# stirrer.net
KiCad netlist of a schematic drawn in EAGLE
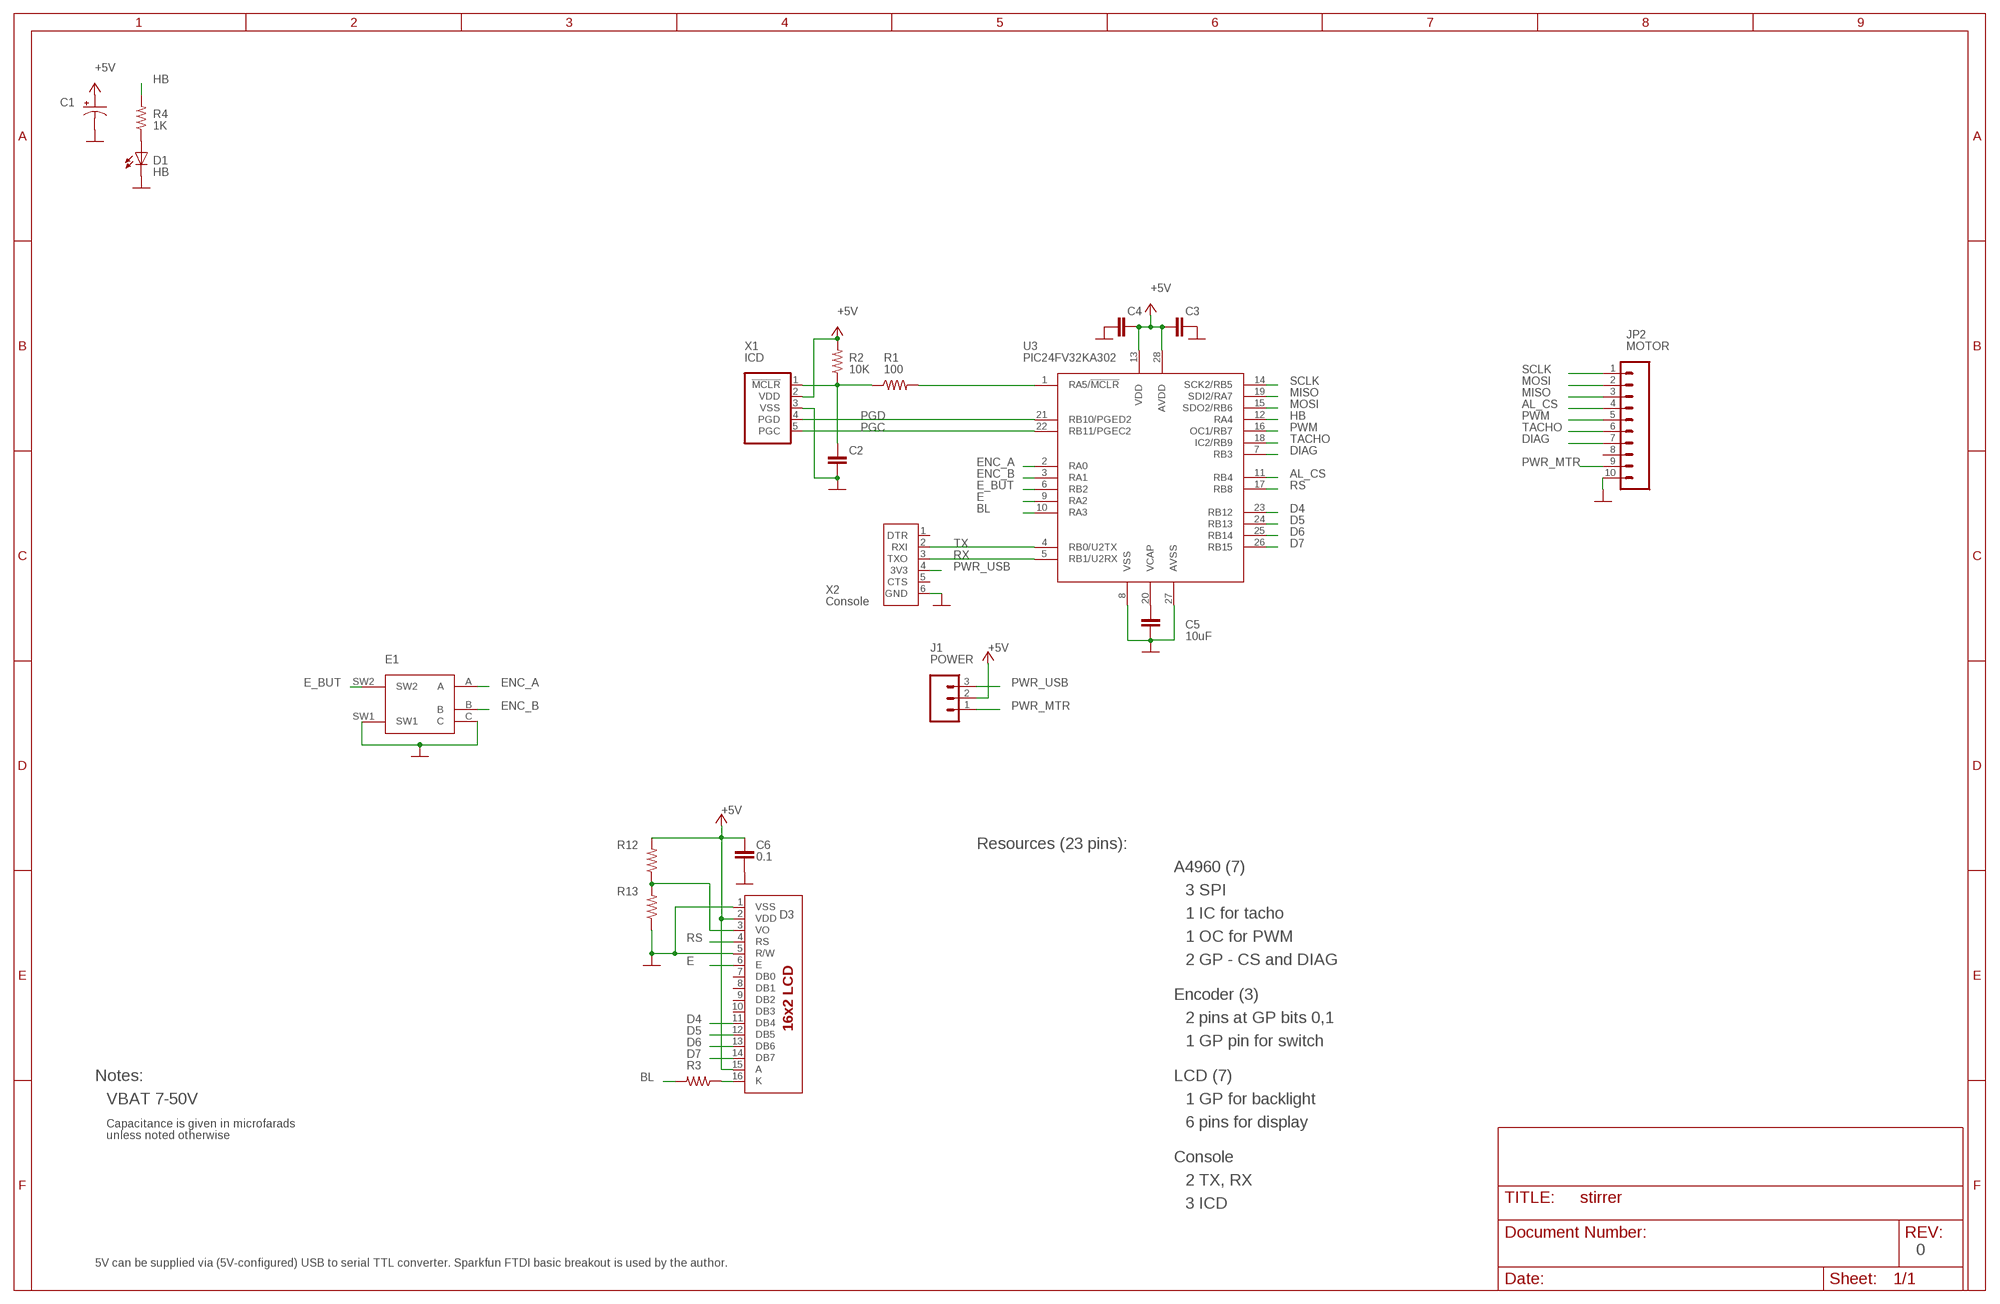
[diagram p0: schematic, sheet 1]

(export (version "E")
  (design (tool "Eeschema 10.0.6"))
  (components
    (comp (ref "C1")
      (value "CAP_POL-RAD4")
      (footprint "eagle-import:CAP_RAD_4MM")
      (libsource (lib "eagle-import") (part "CAP_POL-RAD4"))
    )
    (comp (ref "C2")
      (value "0.1uF")
      (footprint "eagle-import:CAP-PTH-SMALL")
      (libsource (lib "eagle-import") (part "CAPPTH"))
    )
    (comp (ref "C3")
      (value "0.1uF")
      (footprint "eagle-import:CAP-PTH-SMALL")
      (libsource (lib "eagle-import") (part "CAPPTH"))
    )
    (comp (ref "C4")
      (value "0.1uF")
      (footprint "eagle-import:CAP-PTH-SMALL")
      (libsource (lib "eagle-import") (part "CAPPTH"))
    )
    (comp (ref "C5")
      (value "10uF")
      (footprint "eagle-import:CAP-PTH-SMALL")
      (libsource (lib "eagle-import") (part "CAPPTH"))
    )
    (comp (ref "C6")
      (value "0.1")
      (footprint "eagle-import:CAP-PTH-SMALL")
      (libsource (lib "eagle-import") (part "CAPPTH"))
    )
    (comp (ref "D1")
      (value "HB")
      (footprint "eagle-import:LED5MM")
      (libsource (lib "eagle-import") (part "LED5MM"))
    )
    (comp (ref "D3")
      (value "LCD-16X2-STD")
      (footprint "eagle-import:LCD-16X2")
      (libsource (lib "eagle-import") (part "LCD-16X2-STD"))
    )
    (comp (ref "E1")
      (value "ROTARY_ENCODER_SWITCH-PEC12_HOR")
      (footprint "eagle-import:ENC_12X14MM_SW_HOR")
      (libsource (lib "eagle-import") (part "ROTARY_ENCODER_SWITCH-PEC12_HOR"))
    )
    (comp (ref "J1")
      (value "POWER")
      (footprint "eagle-import:1X03")
      (libsource (lib "eagle-import") (part "M03PTH"))
    )
    (comp (ref "JP2")
      (value "MOTOR")
      (footprint "eagle-import:1X10")
      (libsource (lib "eagle-import") (part "M100.1"))
    )
    (comp (ref "R1")
      (value "100")
      (footprint "eagle-import:AXIAL-0.4")
      (libsource (lib "eagle-import") (part "RESISTOR-PTH04"))
    )
    (comp (ref "R2")
      (value "10K")
      (footprint "eagle-import:AXIAL-0.4")
      (libsource (lib "eagle-import") (part "RESISTOR-PTH04"))
    )
    (comp (ref "R3")
      (value "RESISTOR-PTH04")
      (footprint "eagle-import:AXIAL-0.4")
      (libsource (lib "eagle-import") (part "RESISTOR-PTH04"))
    )
    (comp (ref "R4")
      (value "1K")
      (footprint "eagle-import:AXIAL-0.4")
      (libsource (lib "eagle-import") (part "RESISTOR-PTH04"))
    )
    (comp (ref "R12")
      (value "RESISTOR-PTH04")
      (footprint "eagle-import:AXIAL-0.4")
      (libsource (lib "eagle-import") (part "RESISTOR-PTH04"))
    )
    (comp (ref "R13")
      (value "RESISTOR-PTH04")
      (footprint "eagle-import:AXIAL-0.4")
      (libsource (lib "eagle-import") (part "RESISTOR-PTH04"))
    )
    (comp (ref "U3")
      (value "PIC24FV32KA302")
      (footprint "eagle-import:DIL28-3")
      (libsource (lib "eagle-import") (part "PIC24FV32KA302_STIR-DIP"))
    )
    (comp (ref "X1")
      (value "ICD")
      (footprint "eagle-import:1X05")
      (libsource (lib "eagle-import") (part "PIC_ICD-STRAIGHT"))
    )
    (comp (ref "X2")
      (value "Console")
      (footprint "eagle-import:1X06")
      (libsource (lib "eagle-import") (part "SERIAL-SF"))
    )
  )
  (nets
    (net (code "1") (name "+5V") (class "Default")
      (node (ref "C1") (pin "P") (pinfunction "+_P") (pintype "passive"))
      (node (ref "C3") (pin "1") (pinfunction "1_1") (pintype "passive"))
      (node (ref "C4") (pin "2") (pinfunction "2_2") (pintype "passive"))
      (node (ref "C6") (pin "2") (pinfunction "2_2") (pintype "passive"))
      (node (ref "D3") (pin "15") (pinfunction "A_15") (pintype "power_in"))
      (node (ref "D3") (pin "2") (pinfunction "VDD_2") (pintype "power_in"))
      (node (ref "J1") (pin "2") (pinfunction "2_2") (pintype "passive"))
      (node (ref "R12") (pin "P$2") (pinfunction "2_P$2") (pintype "passive"))
      (node (ref "R2") (pin "P$2") (pinfunction "2_P$2") (pintype "passive"))
      (node (ref "U3") (pin "13") (pinfunction "VDD_13") (pintype "bidirectional"))
      (node (ref "U3") (pin "28") (pinfunction "AVDD_28") (pintype "bidirectional"))
      (node (ref "X1") (pin "2") (pinfunction "VDD_2") (pintype "passive"))
    )
    (net (code "2") (name "/AL_CS") (class "Default")
      (node (ref "JP2") (pin "4") (pinfunction "4_4") (pintype "passive"))
      (node (ref "U3") (pin "11") (pinfunction "RB4_11") (pintype "bidirectional"))
    )
    (net (code "3") (name "/BL") (class "Default")
      (node (ref "R3") (pin "P$2") (pinfunction "2_P$2") (pintype "passive"))
      (node (ref "U3") (pin "10") (pinfunction "RA3_10") (pintype "bidirectional"))
    )
    (net (code "4") (name "/D4") (class "Default")
      (node (ref "D3") (pin "11") (pinfunction "DB4_11") (pintype "bidirectional"))
      (node (ref "U3") (pin "23") (pinfunction "RB12_23") (pintype "bidirectional"))
    )
    (net (code "5") (name "/D5") (class "Default")
      (node (ref "D3") (pin "12") (pinfunction "DB5_12") (pintype "bidirectional"))
      (node (ref "U3") (pin "24") (pinfunction "RB13_24") (pintype "bidirectional"))
    )
    (net (code "6") (name "/D6") (class "Default")
      (node (ref "D3") (pin "13") (pinfunction "DB6_13") (pintype "bidirectional"))
      (node (ref "U3") (pin "25") (pinfunction "RB14_25") (pintype "bidirectional"))
    )
    (net (code "7") (name "/D7") (class "Default")
      (node (ref "D3") (pin "14") (pinfunction "DB7_14") (pintype "bidirectional"))
      (node (ref "U3") (pin "26") (pinfunction "RB15_26") (pintype "bidirectional"))
    )
    (net (code "8") (name "/DIAG") (class "Default")
      (node (ref "JP2") (pin "7") (pinfunction "7_7") (pintype "passive"))
      (node (ref "U3") (pin "7") (pinfunction "RB3_7") (pintype "bidirectional"))
    )
    (net (code "9") (name "/E") (class "Default")
      (node (ref "D3") (pin "6") (pinfunction "E_6") (pintype "input"))
      (node (ref "U3") (pin "9") (pinfunction "RA2_9") (pintype "bidirectional"))
    )
    (net (code "10") (name "/ENC_A") (class "Default")
      (node (ref "E1") (pin "A") (pinfunction "A_A") (pintype "passive"))
      (node (ref "U3") (pin "2") (pinfunction "RA0_2") (pintype "bidirectional"))
    )
    (net (code "11") (name "/ENC_B") (class "Default")
      (node (ref "E1") (pin "B") (pinfunction "B_B") (pintype "passive"))
      (node (ref "U3") (pin "3") (pinfunction "RA1_3") (pintype "bidirectional"))
    )
    (net (code "12") (name "/E_BUT") (class "Default")
      (node (ref "E1") (pin "SW2") (pinfunction "SW2_SW2") (pintype "passive"))
      (node (ref "U3") (pin "6") (pinfunction "RB2_6") (pintype "bidirectional"))
    )
    (net (code "13") (name "/HB") (class "Default")
      (node (ref "R4") (pin "P$2") (pinfunction "2_P$2") (pintype "passive"))
      (node (ref "U3") (pin "12") (pinfunction "RA4_12") (pintype "bidirectional"))
    )
    (net (code "14") (name "/MISO") (class "Default")
      (node (ref "JP2") (pin "3") (pinfunction "3_3") (pintype "passive"))
      (node (ref "U3") (pin "19") (pinfunction "SDI2/RA7_19") (pintype "bidirectional"))
    )
    (net (code "15") (name "/MOSI") (class "Default")
      (node (ref "JP2") (pin "2") (pinfunction "2_2") (pintype "passive"))
      (node (ref "U3") (pin "15") (pinfunction "SDO2/RB6_15") (pintype "bidirectional"))
    )
    (net (code "16") (name "/PGC") (class "Default")
      (node (ref "U3") (pin "22") (pinfunction "RB11/PGEC2_22") (pintype "bidirectional"))
      (node (ref "X1") (pin "5") (pinfunction "PGC_5") (pintype "passive"))
    )
    (net (code "17") (name "/PGD") (class "Default")
      (node (ref "U3") (pin "21") (pinfunction "RB10/PGED2_21") (pintype "bidirectional"))
      (node (ref "X1") (pin "4") (pinfunction "PGD_4") (pintype "passive"))
    )
    (net (code "18") (name "/PWM") (class "Default")
      (node (ref "JP2") (pin "5") (pinfunction "5_5") (pintype "passive"))
      (node (ref "U3") (pin "16") (pinfunction "OC1/RB7_16") (pintype "bidirectional"))
    )
    (net (code "19") (name "/PWR_MTR") (class "Default")
      (node (ref "J1") (pin "1") (pinfunction "1_1") (pintype "passive"))
      (node (ref "JP2") (pin "9") (pinfunction "9_9") (pintype "passive"))
    )
    (net (code "20") (name "/PWR_USB") (class "Default")
      (node (ref "J1") (pin "3") (pinfunction "3_3") (pintype "passive"))
      (node (ref "X2") (pin "4") (pinfunction "3V3_4") (pintype "bidirectional"))
    )
    (net (code "21") (name "/RS") (class "Default")
      (node (ref "D3") (pin "4") (pinfunction "RS_4") (pintype "input"))
      (node (ref "U3") (pin "17") (pinfunction "RB8_17") (pintype "bidirectional"))
    )
    (net (code "22") (name "/RX") (class "Default")
      (node (ref "U3") (pin "5") (pinfunction "RB1/U2RX_5") (pintype "bidirectional"))
      (node (ref "X2") (pin "3") (pinfunction "TXO_3") (pintype "bidirectional"))
    )
    (net (code "23") (name "/SCLK") (class "Default")
      (node (ref "JP2") (pin "1") (pinfunction "1_1") (pintype "passive"))
      (node (ref "U3") (pin "14") (pinfunction "SCK2/RB5_14") (pintype "bidirectional"))
    )
    (net (code "24") (name "/TACHO") (class "Default")
      (node (ref "JP2") (pin "6") (pinfunction "6_6") (pintype "passive"))
      (node (ref "U3") (pin "18") (pinfunction "IC2/RB9_18") (pintype "bidirectional"))
    )
    (net (code "25") (name "/TX") (class "Default")
      (node (ref "U3") (pin "4") (pinfunction "RB0/U2TX_4") (pintype "bidirectional"))
      (node (ref "X2") (pin "2") (pinfunction "RXI_2") (pintype "bidirectional"))
    )
    (net (code "26") (name "GND") (class "Default")
      (node (ref "C1") (pin "N") (pinfunction "-_N") (pintype "passive"))
      (node (ref "C2") (pin "1") (pinfunction "1_1") (pintype "passive"))
      (node (ref "C3") (pin "2") (pinfunction "2_2") (pintype "passive"))
      (node (ref "C4") (pin "1") (pinfunction "1_1") (pintype "passive"))
      (node (ref "C5") (pin "2") (pinfunction "2_2") (pintype "passive"))
      (node (ref "C6") (pin "1") (pinfunction "1_1") (pintype "passive"))
      (node (ref "D1") (pin "K") (pinfunction "C_K") (pintype "passive"))
      (node (ref "D3") (pin "1") (pinfunction "VSS_1") (pintype "power_in"))
      (node (ref "D3") (pin "5") (pinfunction "R/W_5") (pintype "input"))
      (node (ref "E1") (pin "C") (pinfunction "C_C") (pintype "passive"))
      (node (ref "E1") (pin "SW1") (pinfunction "SW1_SW1") (pintype "passive"))
      (node (ref "JP2") (pin "10") (pinfunction "10_10") (pintype "passive"))
      (node (ref "R13") (pin "P$1") (pinfunction "1_P$1") (pintype "passive"))
      (node (ref "U3") (pin "27") (pinfunction "AVSS_27") (pintype "bidirectional"))
      (node (ref "U3") (pin "8") (pinfunction "VSS_8") (pintype "bidirectional"))
      (node (ref "X1") (pin "3") (pinfunction "VSS_3") (pintype "passive"))
      (node (ref "X2") (pin "6") (pinfunction "GND_6") (pintype "bidirectional"))
    )
    (net (code "27") (name "Net-(D3-K)") (class "Default")
      (node (ref "D3") (pin "16") (pinfunction "K_16") (pintype "power_in"))
      (node (ref "R3") (pin "P$1") (pinfunction "1_P$1") (pintype "passive"))
    )
    (net (code "28") (name "Net-(D3-VO)") (class "Default")
      (node (ref "D3") (pin "3") (pinfunction "VO_3") (pintype "bidirectional"))
      (node (ref "R12") (pin "P$1") (pinfunction "1_P$1") (pintype "passive"))
      (node (ref "R13") (pin "P$2") (pinfunction "2_P$2") (pintype "passive"))
    )
    (net (code "29") (name "Net-(R1-1)") (class "Default")
      (node (ref "C2") (pin "2") (pinfunction "2_2") (pintype "passive"))
      (node (ref "R1") (pin "P$1") (pinfunction "1_P$1") (pintype "passive"))
      (node (ref "R2") (pin "P$1") (pinfunction "1_P$1") (pintype "passive"))
      (node (ref "X1") (pin "1") (pinfunction "~{MCLR}_1") (pintype "passive"))
    )
    (net (code "30") (name "Net-(R1-2)") (class "Default")
      (node (ref "R1") (pin "P$2") (pinfunction "2_P$2") (pintype "passive"))
      (node (ref "U3") (pin "1") (pinfunction "RA5/~{MCLR}_1") (pintype "bidirectional"))
    )
    (net (code "31") (name "Net-(R4-1)") (class "Default")
      (node (ref "D1") (pin "A") (pinfunction "A_A") (pintype "passive"))
      (node (ref "R4") (pin "P$1") (pinfunction "1_P$1") (pintype "passive"))
    )
    (net (code "32") (name "Net-(U3-VCAP)") (class "Default")
      (node (ref "C5") (pin "1") (pinfunction "1_1") (pintype "passive"))
      (node (ref "U3") (pin "20") (pinfunction "VCAP_20") (pintype "bidirectional"))
    )
    (net (code "33") (name "unconnected-(D3-DB0-Pad7)") (class "Default")
      (node (ref "D3") (pin "7") (pinfunction "DB0_7") (pintype "bidirectional"))
    )
    (net (code "34") (name "unconnected-(D3-DB1-Pad8)") (class "Default")
      (node (ref "D3") (pin "8") (pinfunction "DB1_8") (pintype "bidirectional"))
    )
    (net (code "35") (name "unconnected-(D3-DB2-Pad9)") (class "Default")
      (node (ref "D3") (pin "9") (pinfunction "DB2_9") (pintype "bidirectional"))
    )
    (net (code "36") (name "unconnected-(D3-DB3-Pad10)") (class "Default")
      (node (ref "D3") (pin "10") (pinfunction "DB3_10") (pintype "bidirectional"))
    )
    (net (code "37") (name "unconnected-(JP2-Pad8)") (class "Default")
      (node (ref "JP2") (pin "8") (pinfunction "8_8") (pintype "passive"))
    )
    (net (code "38") (name "unconnected-(X2-CTS-Pad5)") (class "Default")
      (node (ref "X2") (pin "5") (pinfunction "CTS_5") (pintype "bidirectional"))
    )
    (net (code "39") (name "unconnected-(X2-DTR-Pad1)") (class "Default")
      (node (ref "X2") (pin "1") (pinfunction "DTR_1") (pintype "bidirectional"))
    )
  )
)
